# Connectors.net
KiCad netlist of a schematic drawn in Altium Designer
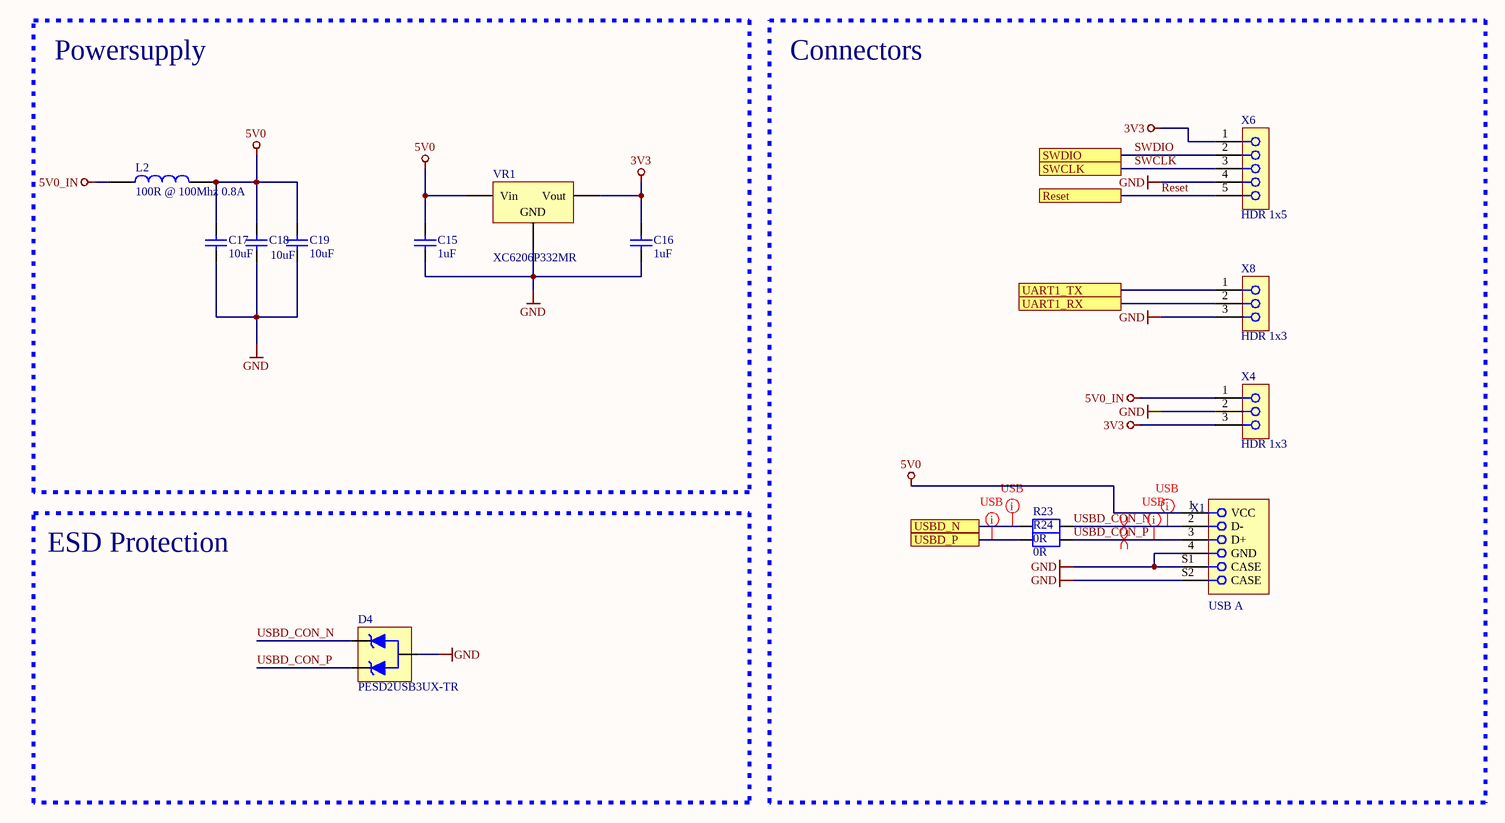
[diagram p0: Connectors.SchDoc]

(export (version "E")
  (design (tool "Eeschema 10.0.6"))
  (components
    (comp (ref "C15")
      (value "1uF")
      (footprint "0603_C")
      (description "Chip capacitors")
      (fields
        (field (name "MANUFACTURER") "Samsung Electro-Mechanics")
        (field (name "PARTNUMBER") "CL10A105KB8NNNC")
      )
      (libsource (lib "Cap") (part "0603 1uF (105) 10% 50V"))
    )
    (comp (ref "C16")
      (value "1uF")
      (footprint "0603_C")
      (description "Chip capacitors")
      (fields
        (field (name "MANUFACTURER") "Samsung Electro-Mechanics")
        (field (name "PARTNUMBER") "CL10A105KB8NNNC")
      )
      (libsource (lib "Cap") (part "0603 1uF (105) 10% 50V"))
    )
    (comp (ref "C17")
      (value "10uF")
      (footprint "0805_C")
      (description "Chip capacitors")
      (fields
        (field (name "MANUFACTURER") "Samsung Electro-Mechanics")
        (field (name "PARTNUMBER") "CL21A106KAYNNNE")
      )
      (libsource (lib "Cap") (part "0805 10uF (106) 10% 25V"))
    )
    (comp (ref "C18")
      (value "10uF")
      (footprint "0805_C")
      (description "Chip capacitors")
      (fields
        (field (name "MANUFACTURER") "Samsung Electro-Mechanics")
        (field (name "PARTNUMBER") "CL21A106KAYNNNE")
      )
      (libsource (lib "Cap") (part "0805 10uF (106) 10% 25V"))
    )
    (comp (ref "C19")
      (value "10uF")
      (footprint "0805_C")
      (description "Chip capacitors")
      (fields
        (field (name "MANUFACTURER") "Samsung Electro-Mechanics")
        (field (name "PARTNUMBER") "CL21A106KAYNNNE")
      )
      (libsource (lib "Cap") (part "0805 10uF (106) 10% 25V"))
    )
    (comp (ref "D4")
      (value "PESD2USB3UX-TR")
      (footprint "SOT95P280X135-3N_123")
      (description "ESD Suppressors / TVS Diodes DIODE ESD PROT")
      (fields (field (name "MANUFACTURER") "Nexperia"))
      (libsource (lib "Diodes") (part "PESD2USB3UX-TR"))
    )
    (comp (ref "L2")
      (value "100R @ 100Mhz 0.8A")
      (footprint "Miscellaneous Devices:6-0805_L")
      (description "Ferrite Bead")
      (libsource (lib "FBEAD") (part "0805 100R@100Mhz 0.8A"))
    )
    (comp (ref "R23")
      (value "0R")
      (footprint "RESC2012X70N")
      (description "Thick Film Resistors - SMD 1/8watt ZEROohm Jumper")
      (fields
        (field (name "MANUFACTURER") "Vishay")
        (field (name "MANUFACTURER PART NUMBER") "CRCW08050000Z0EA")
      )
      (libsource (lib "Resistors") (part "RES_0R_0805"))
    )
    (comp (ref "R24")
      (value "0R")
      (footprint "RESC2012X70N")
      (description "Thick Film Resistors - SMD 1/8watt ZEROohm Jumper")
      (fields
        (field (name "MANUFACTURER") "Vishay")
        (field (name "MANUFACTURER PART NUMBER") "CRCW08050000Z0EA")
      )
      (libsource (lib "Resistors") (part "RES_0R_0805"))
    )
    (comp (ref "VR1")
      (value "XC6206P332MR")
      (footprint "SOT-23-3L")
      (description "低压差线性稳压(LDO)")
      (libsource (lib "LDO") (part "SOT-23 XC6206P332MR"))
    )
    (comp (ref "X1")
      (value "USB A")
      (footprint "CON_USBA_F_61400416021")
      (description "USB 2.0 Type A Horizontal")
      (fields
        (field (name "MANUFACTURER PART NUMBER") "61400416021")
        (field (name "MANUFACTURER") "WURTH ELEKTRONIK")
      )
      (libsource (lib "Connectors") (part "CON_USB_A_FEMALE"))
    )
    (comp (ref "X4")
      (value "HDR 1x3")
      (footprint "CON_HEADER2.54_1x3W")
      (description "Board-to-Board-Steckverbinder, 2.54 mm, 3 Kontakt(e), Stiftleiste 1-Reihig")
      (fields
        (field (name "MANUFACTURER") "Samtec")
        (field (name "MANUFACTURER PART NUMBER") "TSW-103-07-T-S")
      )
      (libsource (lib "_CONNECTORS") (part "CON_HEADER_1X3"))
    )
    (comp (ref "X6")
      (value "HDR 1x5")
      (footprint "CON_HEADER2.54_1x5W")
      (description "Board-to-Board-Steckverbinder, 2.54 mm, 5 Kontakt(e), Stiftleiste 1-Reihig")
      (fields
        (field (name "MANUFACTURER") "Samtec")
        (field (name "MANUFACTURER PART NUMBER") "TSW-105-07-T-S")
      )
      (libsource (lib "_CONNECTORS") (part "CON_HEADER_1X5"))
    )
    (comp (ref "X8")
      (value "HDR 1x3")
      (footprint "CON_HEADER2.54_1x3W")
      (description "Board-to-Board-Steckverbinder, 2.54 mm, 3 Kontakt(e), Stiftleiste 1-Reihig")
      (fields
        (field (name "MANUFACTURER") "Samtec")
        (field (name "MANUFACTURER PART NUMBER") "TSW-103-07-T-S")
      )
      (libsource (lib "_CONNECTORS") (part "CON_HEADER_1X3"))
    )
  )
  (nets
    (net (code "1") (name "/Reset") (class "Default")
      (node (ref "X6") (pin "5") (pinfunction "5_5") (pintype "passive"))
    )
    (net (code "2") (name "/SWCLK") (class "Default")
      (node (ref "X6") (pin "3") (pinfunction "3_3") (pintype "passive"))
    )
    (net (code "3") (name "/SWDIO") (class "Default")
      (node (ref "X6") (pin "2") (pinfunction "2_2") (pintype "passive"))
    )
    (net (code "4") (name "/UART1_RX") (class "Default")
      (node (ref "X8") (pin "2") (pinfunction "2_2") (pintype "passive"))
    )
    (net (code "5") (name "/UART1_TX") (class "Default")
      (node (ref "X8") (pin "1") (pinfunction "1_1") (pintype "passive"))
    )
    (net (code "6") (name "/USBD_CON_N") (class "Default")
      (node (ref "D4") (pin "1") (pinfunction "1_1") (pintype "passive"))
      (node (ref "R23") (pin "2") (pinfunction "2_2") (pintype "passive"))
      (node (ref "X1") (pin "2") (pinfunction "D-_2") (pintype "passive"))
    )
    (net (code "7") (name "/USBD_CON_P") (class "Default")
      (node (ref "D4") (pin "2") (pinfunction "2_2") (pintype "passive"))
      (node (ref "R24") (pin "2") (pinfunction "2_2") (pintype "passive"))
      (node (ref "X1") (pin "3") (pinfunction "D+_3") (pintype "passive"))
    )
    (net (code "8") (name "/USBD_N") (class "Default")
      (node (ref "R23") (pin "1") (pinfunction "1_1") (pintype "passive"))
    )
    (net (code "9") (name "/USBD_P") (class "Default")
      (node (ref "R24") (pin "1") (pinfunction "1_1") (pintype "passive"))
    )
    (net (code "10") (name "3V3") (class "Default")
      (node (ref "C16") (pin "2") (pinfunction "2_2") (pintype "passive"))
      (node (ref "VR1") (pin "2") (pinfunction "Vout_2") (pintype "passive"))
      (node (ref "X4") (pin "3") (pinfunction "3_3") (pintype "passive"))
      (node (ref "X6") (pin "1") (pinfunction "1_1") (pintype "passive"))
    )
    (net (code "11") (name "5V0") (class "Default")
      (node (ref "C15") (pin "2") (pinfunction "2_2") (pintype "passive"))
      (node (ref "C17") (pin "2") (pinfunction "2_2") (pintype "passive"))
      (node (ref "C18") (pin "2") (pinfunction "2_2") (pintype "passive"))
      (node (ref "C19") (pin "2") (pinfunction "2_2") (pintype "passive"))
      (node (ref "L2") (pin "2") (pinfunction "2_2") (pintype "passive"))
      (node (ref "VR1") (pin "3") (pinfunction "Vin_3") (pintype "passive"))
      (node (ref "X1") (pin "1") (pinfunction "VCC_1") (pintype "passive"))
    )
    (net (code "12") (name "5V0_IN") (class "Default")
      (node (ref "L2") (pin "1") (pinfunction "1_1") (pintype "passive"))
      (node (ref "X4") (pin "1") (pinfunction "1_1") (pintype "passive"))
    )
    (net (code "13") (name "GND") (class "Default")
      (node (ref "C15") (pin "1") (pinfunction "1_1") (pintype "passive"))
      (node (ref "C16") (pin "1") (pinfunction "1_1") (pintype "passive"))
      (node (ref "C17") (pin "1") (pinfunction "1_1") (pintype "passive"))
      (node (ref "C18") (pin "1") (pinfunction "1_1") (pintype "passive"))
      (node (ref "C19") (pin "1") (pinfunction "1_1") (pintype "passive"))
      (node (ref "D4") (pin "3") (pinfunction "3_3") (pintype "passive"))
      (node (ref "VR1") (pin "1") (pinfunction "GND_1") (pintype "passive"))
      (node (ref "X1") (pin "4") (pinfunction "GND_4") (pintype "passive"))
      (node (ref "X1") (pin "S1") (pinfunction "CASE_S1") (pintype "passive"))
      (node (ref "X1") (pin "S2") (pinfunction "CASE_S2") (pintype "passive"))
      (node (ref "X4") (pin "2") (pinfunction "2_2") (pintype "passive"))
      (node (ref "X6") (pin "4") (pinfunction "4_4") (pintype "passive"))
      (node (ref "X8") (pin "3") (pinfunction "3_3") (pintype "passive"))
    )
  )
)
